# Digital_Output.net
KiCad netlist of a schematic drawn in Altium Designer
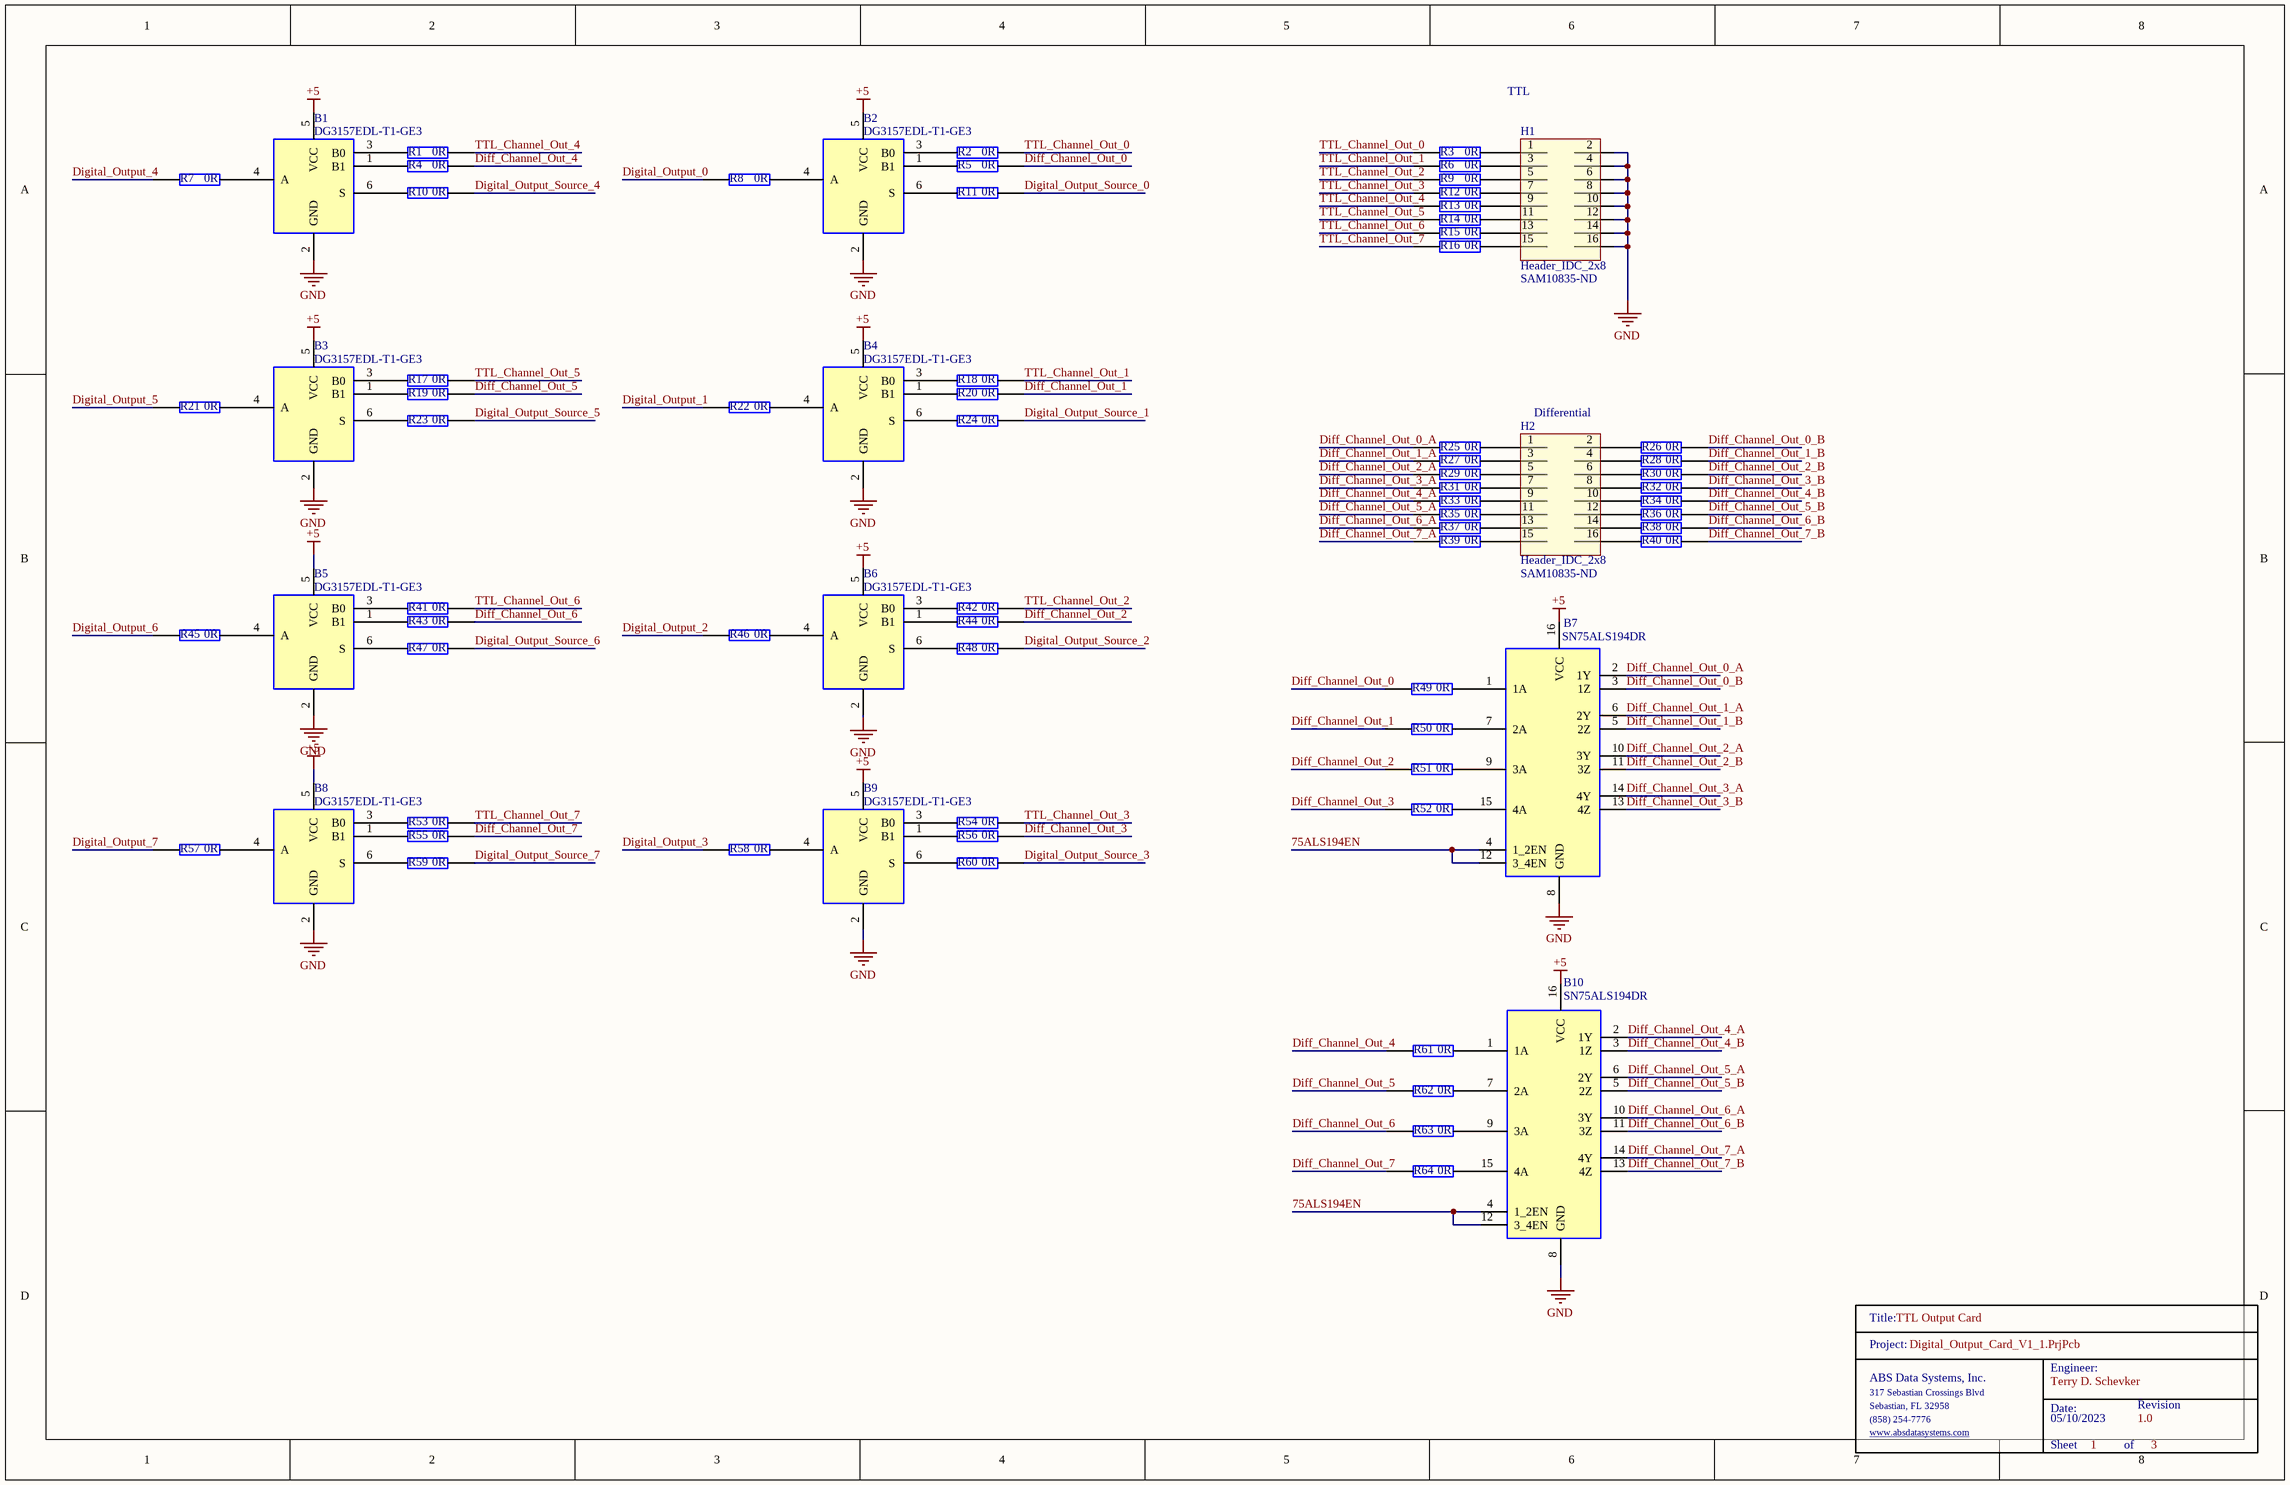
[diagram p0: Digital_Output.SchDoc]

(export (version "E")
  (design (tool "Eeschema 10.0.6"))
  (components
    (comp (ref "B1")
      (value "DG3157EDL-T1-GE3")
      (footprint "SOT65P210X110-6N")
      (description "Vishay DG3157EDL-T1-GE3 Analogue SPDT Switch 1.65 to 5.5 V, 6-Pin SC-70")
      (fields (field (name "MOUSER PART NUMBER") "78-DG3157EDL-T1-GE3"))
      (libsource (lib "SemiConductors") (part "DG3157EDL-T1-GE3"))
    )
    (comp (ref "B2")
      (value "DG3157EDL-T1-GE3")
      (footprint "SOT65P210X110-6N")
      (description "Vishay DG3157EDL-T1-GE3 Analogue SPDT Switch 1.65 to 5.5 V, 6-Pin SC-70")
      (fields (field (name "MOUSER PART NUMBER") "78-DG3157EDL-T1-GE3"))
      (libsource (lib "SemiConductors") (part "DG3157EDL-T1-GE3"))
    )
    (comp (ref "B3")
      (value "DG3157EDL-T1-GE3")
      (footprint "SOT65P210X110-6N")
      (description "Vishay DG3157EDL-T1-GE3 Analogue SPDT Switch 1.65 to 5.5 V, 6-Pin SC-70")
      (fields (field (name "MOUSER PART NUMBER") "78-DG3157EDL-T1-GE3"))
      (libsource (lib "SemiConductors") (part "DG3157EDL-T1-GE3"))
    )
    (comp (ref "B4")
      (value "DG3157EDL-T1-GE3")
      (footprint "SOT65P210X110-6N")
      (description "Vishay DG3157EDL-T1-GE3 Analogue SPDT Switch 1.65 to 5.5 V, 6-Pin SC-70")
      (fields (field (name "MOUSER PART NUMBER") "78-DG3157EDL-T1-GE3"))
      (libsource (lib "SemiConductors") (part "DG3157EDL-T1-GE3"))
    )
    (comp (ref "B5")
      (value "DG3157EDL-T1-GE3")
      (footprint "SOT65P210X110-6N")
      (description "Vishay DG3157EDL-T1-GE3 Analogue SPDT Switch 1.65 to 5.5 V, 6-Pin SC-70")
      (fields (field (name "MOUSER PART NUMBER") "78-DG3157EDL-T1-GE3"))
      (libsource (lib "SemiConductors") (part "DG3157EDL-T1-GE3"))
    )
    (comp (ref "B6")
      (value "DG3157EDL-T1-GE3")
      (footprint "SOT65P210X110-6N")
      (description "Vishay DG3157EDL-T1-GE3 Analogue SPDT Switch 1.65 to 5.5 V, 6-Pin SC-70")
      (fields (field (name "MOUSER PART NUMBER") "78-DG3157EDL-T1-GE3"))
      (libsource (lib "SemiConductors") (part "DG3157EDL-T1-GE3"))
    )
    (comp (ref "B7")
      (value "SN75ALS194DR")
      (footprint "SOIC127P600X175-16N")
      (description "Quadruple Differential Line Driver")
      (fields (field (name "MOUSER PART NUMBER") "595-SN75ALS194DR"))
      (libsource (lib "SemiConductors") (part "SN75ALS194DR"))
    )
    (comp (ref "B8")
      (value "DG3157EDL-T1-GE3")
      (footprint "SOT65P210X110-6N")
      (description "Vishay DG3157EDL-T1-GE3 Analogue SPDT Switch 1.65 to 5.5 V, 6-Pin SC-70")
      (fields (field (name "MOUSER PART NUMBER") "78-DG3157EDL-T1-GE3"))
      (libsource (lib "SemiConductors") (part "DG3157EDL-T1-GE3"))
    )
    (comp (ref "B9")
      (value "DG3157EDL-T1-GE3")
      (footprint "SOT65P210X110-6N")
      (description "Vishay DG3157EDL-T1-GE3 Analogue SPDT Switch 1.65 to 5.5 V, 6-Pin SC-70")
      (fields (field (name "MOUSER PART NUMBER") "78-DG3157EDL-T1-GE3"))
      (libsource (lib "SemiConductors") (part "DG3157EDL-T1-GE3"))
    )
    (comp (ref "B10")
      (value "SN75ALS194DR")
      (footprint "SOIC127P600X175-16N")
      (description "Quadruple Differential Line Driver")
      (fields (field (name "MOUSER PART NUMBER") "595-SN75ALS194DR"))
      (libsource (lib "SemiConductors") (part "SN75ALS194DR"))
    )
    (comp (ref "H1")
      (value "Header_IDC_2x8")
      (footprint "HDR2X8")
      (description "16 Pin 2x8 Through Hold IDC Connector")
      (fields
        (field (name "MANUFACTURER") "Samtec")
        (field (name "MANUFACTURER PART NUMBER") "TST-108-01-G-D")
        (field (name "SUPPLIER PART NUMBER 1") "SAM10835-ND")
      )
      (libsource (lib "Misc") (part "Header_IDC_2x8"))
    )
    (comp (ref "H2")
      (value "Header_IDC_2x8")
      (footprint "HDR2X8")
      (description "16 Pin 2x8 Through Hold IDC Connector")
      (fields
        (field (name "MANUFACTURER") "Samtec")
        (field (name "MANUFACTURER PART NUMBER") "TST-108-01-G-D")
        (field (name "SUPPLIER PART NUMBER 1") "SAM10835-ND")
      )
      (libsource (lib "Misc") (part "Header_IDC_2x8"))
    )
    (comp (ref "R1")
      (value "0R")
      (footprint "0603")
      (description "YAGEO 0603 0 ohm")
      (fields
        (field (name "MOUSER PART NUMBER") "603-RC0603JR-070RL")
        (field (name "MANUFACTURER_PART_NUMBER") "RC0603JR-070RL")
      )
      (libsource (lib "Resistors") (part "RC0603JR-070RL"))
    )
    (comp (ref "R2")
      (value "0R")
      (footprint "0603")
      (description "YAGEO 0603 0 ohm")
      (fields
        (field (name "MOUSER PART NUMBER") "603-RC0603JR-070RL")
        (field (name "MANUFACTURER_PART_NUMBER") "RC0603JR-070RL")
      )
      (libsource (lib "Resistors") (part "RC0603JR-070RL"))
    )
    (comp (ref "R3")
      (value "0R")
      (footprint "0603")
      (description "YAGEO 0603 0 ohm")
      (fields
        (field (name "MOUSER PART NUMBER") "603-RC0603JR-070RL")
        (field (name "MANUFACTURER_PART_NUMBER") "RC0603JR-070RL")
      )
      (libsource (lib "Resistors") (part "RC0603JR-070RL"))
    )
    (comp (ref "R4")
      (value "0R")
      (footprint "0603")
      (description "YAGEO 0603 0 ohm")
      (fields
        (field (name "MOUSER PART NUMBER") "603-RC0603JR-070RL")
        (field (name "MANUFACTURER_PART_NUMBER") "RC0603JR-070RL")
      )
      (libsource (lib "Resistors") (part "RC0603JR-070RL"))
    )
    (comp (ref "R5")
      (value "0R")
      (footprint "0603")
      (description "YAGEO 0603 0 ohm")
      (fields
        (field (name "MOUSER PART NUMBER") "603-RC0603JR-070RL")
        (field (name "MANUFACTURER_PART_NUMBER") "RC0603JR-070RL")
      )
      (libsource (lib "Resistors") (part "RC0603JR-070RL"))
    )
    (comp (ref "R6")
      (value "0R")
      (footprint "0603")
      (description "YAGEO 0603 0 ohm")
      (fields
        (field (name "MOUSER PART NUMBER") "603-RC0603JR-070RL")
        (field (name "MANUFACTURER_PART_NUMBER") "RC0603JR-070RL")
      )
      (libsource (lib "Resistors") (part "RC0603JR-070RL"))
    )
    (comp (ref "R7")
      (value "0R")
      (footprint "0603")
      (description "YAGEO 0603 0 ohm")
      (fields
        (field (name "MOUSER PART NUMBER") "603-RC0603JR-070RL")
        (field (name "MANUFACTURER_PART_NUMBER") "RC0603JR-070RL")
      )
      (libsource (lib "Resistors") (part "RC0603JR-070RL"))
    )
    (comp (ref "R8")
      (value "0R")
      (footprint "0603")
      (description "YAGEO 0603 0 ohm")
      (fields
        (field (name "MOUSER PART NUMBER") "603-RC0603JR-070RL")
        (field (name "MANUFACTURER_PART_NUMBER") "RC0603JR-070RL")
      )
      (libsource (lib "Resistors") (part "RC0603JR-070RL"))
    )
    (comp (ref "R9")
      (value "0R")
      (footprint "0603")
      (description "YAGEO 0603 0 ohm")
      (fields
        (field (name "MOUSER PART NUMBER") "603-RC0603JR-070RL")
        (field (name "MANUFACTURER_PART_NUMBER") "RC0603JR-070RL")
      )
      (libsource (lib "Resistors") (part "RC0603JR-070RL"))
    )
    (comp (ref "R10")
      (value "0R")
      (footprint "0603")
      (description "YAGEO 0603 0 ohm")
      (fields
        (field (name "MOUSER PART NUMBER") "603-RC0603JR-070RL")
        (field (name "MANUFACTURER_PART_NUMBER") "RC0603JR-070RL")
      )
      (libsource (lib "Resistors") (part "RC0603JR-070RL"))
    )
    (comp (ref "R11")
      (value "0R")
      (footprint "0603")
      (description "YAGEO 0603 0 ohm")
      (fields
        (field (name "MOUSER PART NUMBER") "603-RC0603JR-070RL")
        (field (name "MANUFACTURER_PART_NUMBER") "RC0603JR-070RL")
      )
      (libsource (lib "Resistors") (part "RC0603JR-070RL"))
    )
    (comp (ref "R12")
      (value "0R")
      (footprint "0603")
      (description "YAGEO 0603 0 ohm")
      (fields
        (field (name "MOUSER PART NUMBER") "603-RC0603JR-070RL")
        (field (name "MANUFACTURER_PART_NUMBER") "RC0603JR-070RL")
      )
      (libsource (lib "Resistors") (part "RC0603JR-070RL"))
    )
    (comp (ref "R13")
      (value "0R")
      (footprint "0603")
      (description "YAGEO 0603 0 ohm")
      (fields
        (field (name "MOUSER PART NUMBER") "603-RC0603JR-070RL")
        (field (name "MANUFACTURER_PART_NUMBER") "RC0603JR-070RL")
      )
      (libsource (lib "Resistors") (part "RC0603JR-070RL"))
    )
    (comp (ref "R14")
      (value "0R")
      (footprint "0603")
      (description "YAGEO 0603 0 ohm")
      (fields
        (field (name "MOUSER PART NUMBER") "603-RC0603JR-070RL")
        (field (name "MANUFACTURER_PART_NUMBER") "RC0603JR-070RL")
      )
      (libsource (lib "Resistors") (part "RC0603JR-070RL"))
    )
    (comp (ref "R15")
      (value "0R")
      (footprint "0603")
      (description "YAGEO 0603 0 ohm")
      (fields
        (field (name "MOUSER PART NUMBER") "603-RC0603JR-070RL")
        (field (name "MANUFACTURER_PART_NUMBER") "RC0603JR-070RL")
      )
      (libsource (lib "Resistors") (part "RC0603JR-070RL"))
    )
    (comp (ref "R16")
      (value "0R")
      (footprint "0603")
      (description "YAGEO 0603 0 ohm")
      (fields
        (field (name "MOUSER PART NUMBER") "603-RC0603JR-070RL")
        (field (name "MANUFACTURER_PART_NUMBER") "RC0603JR-070RL")
      )
      (libsource (lib "Resistors") (part "RC0603JR-070RL"))
    )
    (comp (ref "R17")
      (value "0R")
      (footprint "0603")
      (description "YAGEO 0603 0 ohm")
      (fields
        (field (name "MOUSER PART NUMBER") "603-RC0603JR-070RL")
        (field (name "MANUFACTURER_PART_NUMBER") "RC0603JR-070RL")
      )
      (libsource (lib "Resistors") (part "RC0603JR-070RL"))
    )
    (comp (ref "R18")
      (value "0R")
      (footprint "0603")
      (description "YAGEO 0603 0 ohm")
      (fields
        (field (name "MOUSER PART NUMBER") "603-RC0603JR-070RL")
        (field (name "MANUFACTURER_PART_NUMBER") "RC0603JR-070RL")
      )
      (libsource (lib "Resistors") (part "RC0603JR-070RL"))
    )
    (comp (ref "R19")
      (value "0R")
      (footprint "0603")
      (description "YAGEO 0603 0 ohm")
      (fields
        (field (name "MOUSER PART NUMBER") "603-RC0603JR-070RL")
        (field (name "MANUFACTURER_PART_NUMBER") "RC0603JR-070RL")
      )
      (libsource (lib "Resistors") (part "RC0603JR-070RL"))
    )
    (comp (ref "R20")
      (value "0R")
      (footprint "0603")
      (description "YAGEO 0603 0 ohm")
      (fields
        (field (name "MOUSER PART NUMBER") "603-RC0603JR-070RL")
        (field (name "MANUFACTURER_PART_NUMBER") "RC0603JR-070RL")
      )
      (libsource (lib "Resistors") (part "RC0603JR-070RL"))
    )
    (comp (ref "R21")
      (value "0R")
      (footprint "0603")
      (description "YAGEO 0603 0 ohm")
      (fields
        (field (name "MOUSER PART NUMBER") "603-RC0603JR-070RL")
        (field (name "MANUFACTURER_PART_NUMBER") "RC0603JR-070RL")
      )
      (libsource (lib "Resistors") (part "RC0603JR-070RL"))
    )
    (comp (ref "R22")
      (value "0R")
      (footprint "0603")
      (description "YAGEO 0603 0 ohm")
      (fields
        (field (name "MOUSER PART NUMBER") "603-RC0603JR-070RL")
        (field (name "MANUFACTURER_PART_NUMBER") "RC0603JR-070RL")
      )
      (libsource (lib "Resistors") (part "RC0603JR-070RL"))
    )
    (comp (ref "R23")
      (value "0R")
      (footprint "0603")
      (description "YAGEO 0603 0 ohm")
      (fields
        (field (name "MOUSER PART NUMBER") "603-RC0603JR-070RL")
        (field (name "MANUFACTURER_PART_NUMBER") "RC0603JR-070RL")
      )
      (libsource (lib "Resistors") (part "RC0603JR-070RL"))
    )
    (comp (ref "R24")
      (value "0R")
      (footprint "0603")
      (description "YAGEO 0603 0 ohm")
      (fields
        (field (name "MOUSER PART NUMBER") "603-RC0603JR-070RL")
        (field (name "MANUFACTURER_PART_NUMBER") "RC0603JR-070RL")
      )
      (libsource (lib "Resistors") (part "RC0603JR-070RL"))
    )
    (comp (ref "R25")
      (value "0R")
      (footprint "0603")
      (description "YAGEO 0603 0 ohm")
      (fields
        (field (name "MOUSER PART NUMBER") "603-RC0603JR-070RL")
        (field (name "MANUFACTURER_PART_NUMBER") "RC0603JR-070RL")
      )
      (libsource (lib "Resistors") (part "RC0603JR-070RL"))
    )
    (comp (ref "R26")
      (value "0R")
      (footprint "0603")
      (description "YAGEO 0603 0 ohm")
      (fields
        (field (name "MOUSER PART NUMBER") "603-RC0603JR-070RL")
        (field (name "MANUFACTURER_PART_NUMBER") "RC0603JR-070RL")
      )
      (libsource (lib "Resistors") (part "RC0603JR-070RL"))
    )
    (comp (ref "R27")
      (value "0R")
      (footprint "0603")
      (description "YAGEO 0603 0 ohm")
      (fields
        (field (name "MOUSER PART NUMBER") "603-RC0603JR-070RL")
        (field (name "MANUFACTURER_PART_NUMBER") "RC0603JR-070RL")
      )
      (libsource (lib "Resistors") (part "RC0603JR-070RL"))
    )
    (comp (ref "R28")
      (value "0R")
      (footprint "0603")
      (description "YAGEO 0603 0 ohm")
      (fields
        (field (name "MOUSER PART NUMBER") "603-RC0603JR-070RL")
        (field (name "MANUFACTURER_PART_NUMBER") "RC0603JR-070RL")
      )
      (libsource (lib "Resistors") (part "RC0603JR-070RL"))
    )
    (comp (ref "R29")
      (value "0R")
      (footprint "0603")
      (description "YAGEO 0603 0 ohm")
      (fields
        (field (name "MOUSER PART NUMBER") "603-RC0603JR-070RL")
        (field (name "MANUFACTURER_PART_NUMBER") "RC0603JR-070RL")
      )
      (libsource (lib "Resistors") (part "RC0603JR-070RL"))
    )
    (comp (ref "R30")
      (value "0R")
      (footprint "0603")
      (description "YAGEO 0603 0 ohm")
      (fields
        (field (name "MOUSER PART NUMBER") "603-RC0603JR-070RL")
        (field (name "MANUFACTURER_PART_NUMBER") "RC0603JR-070RL")
      )
      (libsource (lib "Resistors") (part "RC0603JR-070RL"))
    )
    (comp (ref "R31")
      (value "0R")
      (footprint "0603")
      (description "YAGEO 0603 0 ohm")
      (fields
        (field (name "MOUSER PART NUMBER") "603-RC0603JR-070RL")
        (field (name "MANUFACTURER_PART_NUMBER") "RC0603JR-070RL")
      )
      (libsource (lib "Resistors") (part "RC0603JR-070RL"))
    )
    (comp (ref "R32")
      (value "0R")
      (footprint "0603")
      (description "YAGEO 0603 0 ohm")
      (fields
        (field (name "MOUSER PART NUMBER") "603-RC0603JR-070RL")
        (field (name "MANUFACTURER_PART_NUMBER") "RC0603JR-070RL")
      )
      (libsource (lib "Resistors") (part "RC0603JR-070RL"))
    )
    (comp (ref "R33")
      (value "0R")
      (footprint "0603")
      (description "YAGEO 0603 0 ohm")
      (fields
        (field (name "MOUSER PART NUMBER") "603-RC0603JR-070RL")
        (field (name "MANUFACTURER_PART_NUMBER") "RC0603JR-070RL")
      )
      (libsource (lib "Resistors") (part "RC0603JR-070RL"))
    )
    (comp (ref "R34")
      (value "0R")
      (footprint "0603")
      (description "YAGEO 0603 0 ohm")
      (fields
        (field (name "MOUSER PART NUMBER") "603-RC0603JR-070RL")
        (field (name "MANUFACTURER_PART_NUMBER") "RC0603JR-070RL")
      )
      (libsource (lib "Resistors") (part "RC0603JR-070RL"))
    )
    (comp (ref "R35")
      (value "0R")
      (footprint "0603")
      (description "YAGEO 0603 0 ohm")
      (fields
        (field (name "MOUSER PART NUMBER") "603-RC0603JR-070RL")
        (field (name "MANUFACTURER_PART_NUMBER") "RC0603JR-070RL")
      )
      (libsource (lib "Resistors") (part "RC0603JR-070RL"))
    )
    (comp (ref "R36")
      (value "0R")
      (footprint "0603")
      (description "YAGEO 0603 0 ohm")
      (fields
        (field (name "MOUSER PART NUMBER") "603-RC0603JR-070RL")
        (field (name "MANUFACTURER_PART_NUMBER") "RC0603JR-070RL")
      )
      (libsource (lib "Resistors") (part "RC0603JR-070RL"))
    )
    (comp (ref "R37")
      (value "0R")
      (footprint "0603")
      (description "YAGEO 0603 0 ohm")
      (fields
        (field (name "MOUSER PART NUMBER") "603-RC0603JR-070RL")
        (field (name "MANUFACTURER_PART_NUMBER") "RC0603JR-070RL")
      )
      (libsource (lib "Resistors") (part "RC0603JR-070RL"))
    )
    (comp (ref "R38")
      (value "0R")
      (footprint "0603")
      (description "YAGEO 0603 0 ohm")
      (fields
        (field (name "MOUSER PART NUMBER") "603-RC0603JR-070RL")
        (field (name "MANUFACTURER_PART_NUMBER") "RC0603JR-070RL")
      )
      (libsource (lib "Resistors") (part "RC0603JR-070RL"))
    )
    (comp (ref "R39")
      (value "0R")
      (footprint "0603")
      (description "YAGEO 0603 0 ohm")
      (fields
        (field (name "MOUSER PART NUMBER") "603-RC0603JR-070RL")
        (field (name "MANUFACTURER_PART_NUMBER") "RC0603JR-070RL")
      )
      (libsource (lib "Resistors") (part "RC0603JR-070RL"))
    )
    (comp (ref "R40")
      (value "0R")
      (footprint "0603")
      (description "YAGEO 0603 0 ohm")
      (fields
        (field (name "MOUSER PART NUMBER") "603-RC0603JR-070RL")
        (field (name "MANUFACTURER_PART_NUMBER") "RC0603JR-070RL")
      )
      (libsource (lib "Resistors") (part "RC0603JR-070RL"))
    )
    (comp (ref "R41")
      (value "0R")
      (footprint "0603")
      (description "YAGEO 0603 0 ohm")
      (fields
        (field (name "MOUSER PART NUMBER") "603-RC0603JR-070RL")
        (field (name "MANUFACTURER_PART_NUMBER") "RC0603JR-070RL")
      )
      (libsource (lib "Resistors") (part "RC0603JR-070RL"))
    )
    (comp (ref "R42")
      (value "0R")
      (footprint "0603")
      (description "YAGEO 0603 0 ohm")
      (fields
        (field (name "MOUSER PART NUMBER") "603-RC0603JR-070RL")
        (field (name "MANUFACTURER_PART_NUMBER") "RC0603JR-070RL")
      )
      (libsource (lib "Resistors") (part "RC0603JR-070RL"))
    )
    (comp (ref "R43")
      (value "0R")
      (footprint "0603")
      (description "YAGEO 0603 0 ohm")
      (fields
        (field (name "MOUSER PART NUMBER") "603-RC0603JR-070RL")
        (field (name "MANUFACTURER_PART_NUMBER") "RC0603JR-070RL")
      )
      (libsource (lib "Resistors") (part "RC0603JR-070RL"))
    )
    (comp (ref "R44")
      (value "0R")
      (footprint "0603")
      (description "YAGEO 0603 0 ohm")
      (fields
        (field (name "MOUSER PART NUMBER") "603-RC0603JR-070RL")
        (field (name "MANUFACTURER_PART_NUMBER") "RC0603JR-070RL")
      )
      (libsource (lib "Resistors") (part "RC0603JR-070RL"))
    )
    (comp (ref "R45")
      (value "0R")
      (footprint "0603")
      (description "YAGEO 0603 0 ohm")
      (fields
        (field (name "MOUSER PART NUMBER") "603-RC0603JR-070RL")
        (field (name "MANUFACTURER_PART_NUMBER") "RC0603JR-070RL")
      )
      (libsource (lib "Resistors") (part "RC0603JR-070RL"))
    )
    (comp (ref "R46")
      (value "0R")
      (footprint "0603")
      (description "YAGEO 0603 0 ohm")
      (fields
        (field (name "MOUSER PART NUMBER") "603-RC0603JR-070RL")
        (field (name "MANUFACTURER_PART_NUMBER") "RC0603JR-070RL")
      )
      (libsource (lib "Resistors") (part "RC0603JR-070RL"))
    )
    (comp (ref "R47")
      (value "0R")
      (footprint "0603")
      (description "YAGEO 0603 0 ohm")
      (fields
        (field (name "MOUSER PART NUMBER") "603-RC0603JR-070RL")
        (field (name "MANUFACTURER_PART_NUMBER") "RC0603JR-070RL")
      )
      (libsource (lib "Resistors") (part "RC0603JR-070RL"))
    )
    (comp (ref "R48")
      (value "0R")
      (footprint "0603")
      (description "YAGEO 0603 0 ohm")
      (fields
        (field (name "MOUSER PART NUMBER") "603-RC0603JR-070RL")
        (field (name "MANUFACTURER_PART_NUMBER") "RC0603JR-070RL")
      )
      (libsource (lib "Resistors") (part "RC0603JR-070RL"))
    )
    (comp (ref "R49")
      (value "0R")
      (footprint "0603")
      (description "YAGEO 0603 0 ohm")
      (fields
        (field (name "MOUSER PART NUMBER") "603-RC0603JR-070RL")
        (field (name "MANUFACTURER_PART_NUMBER") "RC0603JR-070RL")
      )
      (libsource (lib "Resistors") (part "RC0603JR-070RL"))
    )
    (comp (ref "R50")
      (value "0R")
      (footprint "0603")
      (description "YAGEO 0603 0 ohm")
      (fields
        (field (name "MOUSER PART NUMBER") "603-RC0603JR-070RL")
        (field (name "MANUFACTURER_PART_NUMBER") "RC0603JR-070RL")
      )
      (libsource (lib "Resistors") (part "RC0603JR-070RL"))
    )
    (comp (ref "R51")
      (value "0R")
      (footprint "0603")
      (description "YAGEO 0603 0 ohm")
      (fields
        (field (name "MOUSER PART NUMBER") "603-RC0603JR-070RL")
        (field (name "MANUFACTURER_PART_NUMBER") "RC0603JR-070RL")
      )
      (libsource (lib "Resistors") (part "RC0603JR-070RL"))
    )
    (comp (ref "R52")
      (value "0R")
      (footprint "0603")
      (description "YAGEO 0603 0 ohm")
      (fields
        (field (name "MOUSER PART NUMBER") "603-RC0603JR-070RL")
        (field (name "MANUFACTURER_PART_NUMBER") "RC0603JR-070RL")
      )
      (libsource (lib "Resistors") (part "RC0603JR-070RL"))
    )
    (comp (ref "R53")
      (value "0R")
      (footprint "0603")
      (description "YAGEO 0603 0 ohm")
      (fields
        (field (name "MOUSER PART NUMBER") "603-RC0603JR-070RL")
        (field (name "MANUFACTURER_PART_NUMBER") "RC0603JR-070RL")
      )
      (libsource (lib "Resistors") (part "RC0603JR-070RL"))
    )
    (comp (ref "R54")
      (value "0R")
      (footprint "0603")
      (description "YAGEO 0603 0 ohm")
      (fields
        (field (name "MOUSER PART NUMBER") "603-RC0603JR-070RL")
        (field (name "MANUFACTURER_PART_NUMBER") "RC0603JR-070RL")
      )
      (libsource (lib "Resistors") (part "RC0603JR-070RL"))
    )
    (comp (ref "R55")
      (value "0R")
      (footprint "0603")
      (description "YAGEO 0603 0 ohm")
      (fields
        (field (name "MOUSER PART NUMBER") "603-RC0603JR-070RL")
        (field (name "MANUFACTURER_PART_NUMBER") "RC0603JR-070RL")
      )
      (libsource (lib "Resistors") (part "RC0603JR-070RL"))
    )
    (comp (ref "R56")
      (value "0R")
      (footprint "0603")
      (description "YAGEO 0603 0 ohm")
      (fields
        (field (name "MOUSER PART NUMBER") "603-RC0603JR-070RL")
        (field (name "MANUFACTURER_PART_NUMBER") "RC0603JR-070RL")
      )
      (libsource (lib "Resistors") (part "RC0603JR-070RL"))
    )
    (comp (ref "R57")
      (value "0R")
      (footprint "0603")
      (description "YAGEO 0603 0 ohm")
      (fields
        (field (name "MOUSER PART NUMBER") "603-RC0603JR-070RL")
        (field (name "MANUFACTURER_PART_NUMBER") "RC0603JR-070RL")
      )
      (libsource (lib "Resistors") (part "RC0603JR-070RL"))
    )
    (comp (ref "R58")
      (value "0R")
      (footprint "0603")
      (description "YAGEO 0603 0 ohm")
      (fields
        (field (name "MOUSER PART NUMBER") "603-RC0603JR-070RL")
        (field (name "MANUFACTURER_PART_NUMBER") "RC0603JR-070RL")
      )
      (libsource (lib "Resistors") (part "RC0603JR-070RL"))
    )
    (comp (ref "R59")
      (value "0R")
      (footprint "0603")
      (description "YAGEO 0603 0 ohm")
      (fields
        (field (name "MOUSER PART NUMBER") "603-RC0603JR-070RL")
        (field (name "MANUFACTURER_PART_NUMBER") "RC0603JR-070RL")
      )
      (libsource (lib "Resistors") (part "RC0603JR-070RL"))
    )
    (comp (ref "R60")
      (value "0R")
      (footprint "0603")
      (description "YAGEO 0603 0 ohm")
      (fields
        (field (name "MOUSER PART NUMBER") "603-RC0603JR-070RL")
        (field (name "MANUFACTURER_PART_NUMBER") "RC0603JR-070RL")
      )
      (libsource (lib "Resistors") (part "RC0603JR-070RL"))
    )
    (comp (ref "R61")
      (value "0R")
      (footprint "0603")
      (description "YAGEO 0603 0 ohm")
      (fields
        (field (name "MOUSER PART NUMBER") "603-RC0603JR-070RL")
        (field (name "MANUFACTURER_PART_NUMBER") "RC0603JR-070RL")
      )
      (libsource (lib "Resistors") (part "RC0603JR-070RL"))
    )
    (comp (ref "R62")
      (value "0R")
      (footprint "0603")
      (description "YAGEO 0603 0 ohm")
      (fields
        (field (name "MOUSER PART NUMBER") "603-RC0603JR-070RL")
        (field (name "MANUFACTURER_PART_NUMBER") "RC0603JR-070RL")
      )
      (libsource (lib "Resistors") (part "RC0603JR-070RL"))
    )
    (comp (ref "R63")
      (value "0R")
      (footprint "0603")
      (description "YAGEO 0603 0 ohm")
      (fields
        (field (name "MOUSER PART NUMBER") "603-RC0603JR-070RL")
        (field (name "MANUFACTURER_PART_NUMBER") "RC0603JR-070RL")
      )
      (libsource (lib "Resistors") (part "RC0603JR-070RL"))
    )
    (comp (ref "R64")
      (value "0R")
      (footprint "0603")
      (description "YAGEO 0603 0 ohm")
      (fields
        (field (name "MOUSER PART NUMBER") "603-RC0603JR-070RL")
        (field (name "MANUFACTURER_PART_NUMBER") "RC0603JR-070RL")
      )
      (libsource (lib "Resistors") (part "RC0603JR-070RL"))
    )
    (comp (ref "TitleBlock_3") (value "TitleBlock") (libsource (lib "Misc") (part "TitleBlock")))
  )
  (nets
    (net (code "1") (name "+5") (class "Default")
      (node (ref "B1") (pin "5") (pinfunction "VCC_5") (pintype "passive"))
      (node (ref "B10") (pin "16") (pinfunction "VCC_16") (pintype "passive"))
      (node (ref "B2") (pin "5") (pinfunction "VCC_5") (pintype "passive"))
      (node (ref "B3") (pin "5") (pinfunction "VCC_5") (pintype "passive"))
      (node (ref "B4") (pin "5") (pinfunction "VCC_5") (pintype "passive"))
      (node (ref "B5") (pin "5") (pinfunction "VCC_5") (pintype "passive"))
      (node (ref "B6") (pin "5") (pinfunction "VCC_5") (pintype "passive"))
      (node (ref "B7") (pin "16") (pinfunction "VCC_16") (pintype "passive"))
      (node (ref "B8") (pin "5") (pinfunction "VCC_5") (pintype "passive"))
      (node (ref "B9") (pin "5") (pinfunction "VCC_5") (pintype "passive"))
    )
    (net (code "2") (name "/75ALS194EN") (class "Default")
      (node (ref "B10") (pin "12") (pinfunction "3_4EN_12") (pintype "passive"))
      (node (ref "B10") (pin "4") (pinfunction "1_2EN_4") (pintype "passive"))
      (node (ref "B7") (pin "12") (pinfunction "3_4EN_12") (pintype "passive"))
      (node (ref "B7") (pin "4") (pinfunction "1_2EN_4") (pintype "passive"))
    )
    (net (code "3") (name "/Diff_Channel_Out_0") (class "Default")
      (node (ref "R49") (pin "1") (pinfunction "1_1") (pintype "passive"))
      (node (ref "R5") (pin "2") (pinfunction "2_2") (pintype "passive"))
    )
    (net (code "4") (name "/Diff_Channel_Out_0_A") (class "Default")
      (node (ref "B7") (pin "2") (pinfunction "1Y_2") (pintype "passive"))
      (node (ref "R25") (pin "1") (pinfunction "1_1") (pintype "passive"))
    )
    (net (code "5") (name "/Diff_Channel_Out_0_B") (class "Default")
      (node (ref "B7") (pin "3") (pinfunction "1Z_3") (pintype "passive"))
      (node (ref "R26") (pin "2") (pinfunction "2_2") (pintype "passive"))
    )
    (net (code "6") (name "/Diff_Channel_Out_1") (class "Default")
      (node (ref "R20") (pin "2") (pinfunction "2_2") (pintype "passive"))
      (node (ref "R50") (pin "1") (pinfunction "1_1") (pintype "passive"))
    )
    (net (code "7") (name "/Diff_Channel_Out_1_A") (class "Default")
      (node (ref "B7") (pin "6") (pinfunction "2Y_6") (pintype "passive"))
      (node (ref "R27") (pin "1") (pinfunction "1_1") (pintype "passive"))
    )
    (net (code "8") (name "/Diff_Channel_Out_1_B") (class "Default")
      (node (ref "B7") (pin "5") (pinfunction "2Z_5") (pintype "passive"))
      (node (ref "R28") (pin "2") (pinfunction "2_2") (pintype "passive"))
    )
    (net (code "9") (name "/Diff_Channel_Out_2") (class "Default")
      (node (ref "R44") (pin "2") (pinfunction "2_2") (pintype "passive"))
      (node (ref "R51") (pin "1") (pinfunction "1_1") (pintype "passive"))
    )
    (net (code "10") (name "/Diff_Channel_Out_2_A") (class "Default")
      (node (ref "B7") (pin "10") (pinfunction "3Y_10") (pintype "passive"))
      (node (ref "R29") (pin "1") (pinfunction "1_1") (pintype "passive"))
    )
    (net (code "11") (name "/Diff_Channel_Out_2_B") (class "Default")
      (node (ref "B7") (pin "11") (pinfunction "3Z_11") (pintype "passive"))
      (node (ref "R30") (pin "2") (pinfunction "2_2") (pintype "passive"))
    )
    (net (code "12") (name "/Diff_Channel_Out_3") (class "Default")
      (node (ref "R52") (pin "1") (pinfunction "1_1") (pintype "passive"))
      (node (ref "R56") (pin "2") (pinfunction "2_2") (pintype "passive"))
    )
    (net (code "13") (name "/Diff_Channel_Out_3_A") (class "Default")
      (node (ref "B7") (pin "14") (pinfunction "4Y_14") (pintype "passive"))
      (node (ref "R31") (pin "1") (pinfunction "1_1") (pintype "passive"))
    )
    (net (code "14") (name "/Diff_Channel_Out_3_B") (class "Default")
      (node (ref "B7") (pin "13") (pinfunction "4Z_13") (pintype "passive"))
      (node (ref "R32") (pin "2") (pinfunction "2_2") (pintype "passive"))
    )
    (net (code "15") (name "/Diff_Channel_Out_4") (class "Default")
      (node (ref "R4") (pin "2") (pinfunction "2_2") (pintype "passive"))
      (node (ref "R61") (pin "1") (pinfunction "1_1") (pintype "passive"))
    )
    (net (code "16") (name "/Diff_Channel_Out_4_A") (class "Default")
      (node (ref "B10") (pin "2") (pinfunction "1Y_2") (pintype "passive"))
      (node (ref "R33") (pin "1") (pinfunction "1_1") (pintype "passive"))
    )
    (net (code "17") (name "/Diff_Channel_Out_4_B") (class "Default")
      (node (ref "B10") (pin "3") (pinfunction "1Z_3") (pintype "passive"))
      (node (ref "R34") (pin "2") (pinfunction "2_2") (pintype "passive"))
    )
    (net (code "18") (name "/Diff_Channel_Out_5") (class "Default")
      (node (ref "R19") (pin "2") (pinfunction "2_2") (pintype "passive"))
      (node (ref "R62") (pin "1") (pinfunction "1_1") (pintype "passive"))
    )
    (net (code "19") (name "/Diff_Channel_Out_5_A") (class "Default")
      (node (ref "B10") (pin "6") (pinfunction "2Y_6") (pintype "passive"))
      (node (ref "R35") (pin "1") (pinfunction "1_1") (pintype "passive"))
    )
    (net (code "20") (name "/Diff_Channel_Out_5_B") (class "Default")
      (node (ref "B10") (pin "5") (pinfunction "2Z_5") (pintype "passive"))
      (node (ref "R36") (pin "2") (pinfunction "2_2") (pintype "passive"))
    )
    (net (code "21") (name "/Diff_Channel_Out_6") (class "Default")
      (node (ref "R43") (pin "2") (pinfunction "2_2") (pintype "passive"))
      (node (ref "R63") (pin "1") (pinfunction "1_1") (pintype "passive"))
    )
    (net (code "22") (name "/Diff_Channel_Out_6_A") (class "Default")
      (node (ref "B10") (pin "10") (pinfunction "3Y_10") (pintype "passive"))
      (node (ref "R37") (pin "1") (pinfunction "1_1") (pintype "passive"))
    )
    (net (code "23") (name "/Diff_Channel_Out_6_B") (class "Default")
      (node (ref "B10") (pin "11") (pinfunction "3Z_11") (pintype "passive"))
      (node (ref "R38") (pin "2") (pinfunction "2_2") (pintype "passive"))
    )
    (net (code "24") (name "/Diff_Channel_Out_7") (class "Default")
      (node (ref "R55") (pin "2") (pinfunction "2_2") (pintype "passive"))
      (node (ref "R64") (pin "1") (pinfunction "1_1") (pintype "passive"))
    )
    (net (code "25") (name "/Diff_Channel_Out_7_A") (class "Default")
      (node (ref "B10") (pin "14") (pinfunction "4Y_14") (pintype "passive"))
      (node (ref "R39") (pin "1") (pinfunction "1_1") (pintype "passive"))
    )
    (net (code "26") (name "/Diff_Channel_Out_7_B") (class "Default")
      (node (ref "B10") (pin "13") (pinfunction "4Z_13") (pintype "passive"))
      (node (ref "R40") (pin "2") (pinfunction "2_2") (pintype "passive"))
    )
    (net (code "27") (name "/Digital_Output_0") (class "Default")
      (node (ref "R8") (pin "1") (pinfunction "1_1") (pintype "passive"))
    )
    (net (code "28") (name "/Digital_Output_1") (class "Default")
      (node (ref "R22") (pin "1") (pinfunction "1_1") (pintype "passive"))
    )
    (net (code "29") (name "/Digital_Output_2") (class "Default")
      (node (ref "R46") (pin "1") (pinfunction "1_1") (pintype "passive"))
    )
    (net (code "30") (name "/Digital_Output_3") (class "Default")
      (node (ref "R58") (pin "1") (pinfunction "1_1") (pintype "passive"))
    )
    (net (code "31") (name "/Digital_Output_4") (class "Default")
      (node (ref "R7") (pin "1") (pinfunction "1_1") (pintype "passive"))
    )
    (net (code "32") (name "/Digital_Output_5") (class "Default")
      (node (ref "R21") (pin "1") (pinfunction "1_1") (pintype "passive"))
    )
    (net (code "33") (name "/Digital_Output_6") (class "Default")
      (node (ref "R45") (pin "1") (pinfunction "1_1") (pintype "passive"))
    )
    (net (code "34") (name "/Digital_Output_7") (class "Default")
      (node (ref "R57") (pin "1") (pinfunction "1_1") (pintype "passive"))
    )
    (net (code "35") (name "/Digital_Output_Source_0") (class "Default")
      (node (ref "R11") (pin "2") (pinfunction "2_2") (pintype "passive"))
    )
    (net (code "36") (name "/Digital_Output_Source_1") (class "Default")
      (node (ref "R24") (pin "2") (pinfunction "2_2") (pintype "passive"))
    )
    (net (code "37") (name "/Digital_Output_Source_2") (class "Default")
      (node (ref "R48") (pin "2") (pinfunction "2_2") (pintype "passive"))
    )
    (net (code "38") (name "/Digital_Output_Source_3") (class "Default")
      (node (ref "R60") (pin "2") (pinfunction "2_2") (pintype "passive"))
    )
    (net (code "39") (name "/Digital_Output_Source_4") (class "Default")
      (node (ref "R10") (pin "2") (pinfunction "2_2") (pintype "passive"))
    )
    (net (code "40") (name "/Digital_Output_Source_5") (class "Default")
      (node (ref "R23") (pin "2") (pinfunction "2_2") (pintype "passive"))
    )
    (net (code "41") (name "/Digital_Output_Source_6") (class "Default")
      (node (ref "R47") (pin "2") (pinfunction "2_2") (pintype "passive"))
    )
    (net (code "42") (name "/Digital_Output_Source_7") (class "Default")
      (node (ref "R59") (pin "2") (pinfunction "2_2") (pintype "passive"))
    )
    (net (code "43") (name "/TTL_Channel_Out_0") (class "Default")
      (node (ref "R2") (pin "2") (pinfunction "2_2") (pintype "passive"))
      (node (ref "R3") (pin "1") (pinfunction "1_1") (pintype "passive"))
    )
    (net (code "44") (name "/TTL_Channel_Out_1") (class "Default")
      (node (ref "R18") (pin "2") (pinfunction "2_2") (pintype "passive"))
      (node (ref "R6") (pin "1") (pinfunction "1_1") (pintype "passive"))
    )
    (net (code "45") (name "/TTL_Channel_Out_2") (class "Default")
      (node (ref "R42") (pin "2") (pinfunction "2_2") (pintype "passive"))
      (node (ref "R9") (pin "1") (pinfunction "1_1") (pintype "passive"))
    )
    (net (code "46") (name "/TTL_Channel_Out_3") (class "Default")
      (node (ref "R12") (pin "1") (pinfunction "1_1") (pintype "passive"))
      (node (ref "R54") (pin "2") (pinfunction "2_2") (pintype "passive"))
    )
    (net (code "47") (name "/TTL_Channel_Out_4") (class "Default")
      (node (ref "R1") (pin "2") (pinfunction "2_2") (pintype "passive"))
      (node (ref "R13") (pin "1") (pinfunction "1_1") (pintype "passive"))
    )
    (net (code "48") (name "/TTL_Channel_Out_5") (class "Default")
      (node (ref "R14") (pin "1") (pinfunction "1_1") (pintype "passive"))
      (node (ref "R17") (pin "2") (pinfunction "2_2") (pintype "passive"))
    )
    (net (code "49") (name "/TTL_Channel_Out_6") (class "Default")
      (node (ref "R15") (pin "1") (pinfunction "1_1") (pintype "passive"))
      (node (ref "R41") (pin "2") (pinfunction "2_2") (pintype "passive"))
    )
    (net (code "50") (name "/TTL_Channel_Out_7") (class "Default")
      (node (ref "R16") (pin "1") (pinfunction "1_1") (pintype "passive"))
      (node (ref "R53") (pin "2") (pinfunction "2_2") (pintype "passive"))
    )
    (net (code "51") (name "GND") (class "Default")
      (node (ref "B1") (pin "2") (pinfunction "GND_2") (pintype "passive"))
      (node (ref "B10") (pin "8") (pinfunction "GND_8") (pintype "passive"))
      (node (ref "B2") (pin "2") (pinfunction "GND_2") (pintype "passive"))
      (node (ref "B3") (pin "2") (pinfunction "GND_2") (pintype "passive"))
      (node (ref "B4") (pin "2") (pinfunction "GND_2") (pintype "passive"))
      (node (ref "B5") (pin "2") (pinfunction "GND_2") (pintype "passive"))
      (node (ref "B6") (pin "2") (pinfunction "GND_2") (pintype "passive"))
      (node (ref "B7") (pin "8") (pinfunction "GND_8") (pintype "passive"))
      (node (ref "B8") (pin "2") (pinfunction "GND_2") (pintype "passive"))
      (node (ref "B9") (pin "2") (pinfunction "GND_2") (pintype "passive"))
      (node (ref "H1") (pin "10") (pinfunction "10_10") (pintype "passive"))
      (node (ref "H1") (pin "12") (pinfunction "12_12") (pintype "passive"))
      (node (ref "H1") (pin "14") (pinfunction "14_14") (pintype "passive"))
      (node (ref "H1") (pin "16") (pinfunction "16_16") (pintype "passive"))
      (node (ref "H1") (pin "2") (pinfunction "2_2") (pintype "passive"))
      (node (ref "H1") (pin "4") (pinfunction "4_4") (pintype "passive"))
      (node (ref "H1") (pin "6") (pinfunction "6_6") (pintype "passive"))
      (node (ref "H1") (pin "8") (pinfunction "8_8") (pintype "passive"))
    )
    (net (code "52") (name "Net-(B1-A)") (class "Default")
      (node (ref "B1") (pin "4") (pinfunction "A_4") (pintype "passive"))
      (node (ref "R7") (pin "2") (pinfunction "2_2") (pintype "passive"))
    )
    (net (code "53") (name "Net-(B1-B0)") (class "Default")
      (node (ref "B1") (pin "3") (pinfunction "B0_3") (pintype "passive"))
      (node (ref "R1") (pin "1") (pinfunction "1_1") (pintype "passive"))
    )
    (net (code "54") (name "Net-(B1-B1)") (class "Default")
      (node (ref "B1") (pin "1") (pinfunction "B1_1") (pintype "passive"))
      (node (ref "R4") (pin "1") (pinfunction "1_1") (pintype "passive"))
    )
    (net (code "55") (name "Net-(B1-S)") (class "Default")
      (node (ref "B1") (pin "6") (pinfunction "S_6") (pintype "passive"))
      (node (ref "R10") (pin "1") (pinfunction "1_1") (pintype "passive"))
    )
    (net (code "56") (name "Net-(B2-A)") (class "Default")
      (node (ref "B2") (pin "4") (pinfunction "A_4") (pintype "passive"))
      (node (ref "R8") (pin "2") (pinfunction "2_2") (pintype "passive"))
    )
    (net (code "57") (name "Net-(B2-B0)") (class "Default")
      (node (ref "B2") (pin "3") (pinfunction "B0_3") (pintype "passive"))
      (node (ref "R2") (pin "1") (pinfunction "1_1") (pintype "passive"))
    )
    (net (code "58") (name "Net-(B2-B1)") (class "Default")
      (node (ref "B2") (pin "1") (pinfunction "B1_1") (pintype "passive"))
      (node (ref "R5") (pin "1") (pinfunction "1_1") (pintype "passive"))
    )
    (net (code "59") (name "Net-(B2-S)") (class "Default")
      (node (ref "B2") (pin "6") (pinfunction "S_6") (pintype "passive"))
      (node (ref "R11") (pin "1") (pinfunction "1_1") (pintype "passive"))
    )
    (net (code "60") (name "Net-(B3-A)") (class "Default")
      (node (ref "B3") (pin "4") (pinfunction "A_4") (pintype "passive"))
      (node (ref "R21") (pin "2") (pinfunction "2_2") (pintype "passive"))
    )
    (net (code "61") (name "Net-(B3-B0)") (class "Default")
      (node (ref "B3") (pin "3") (pinfunction "B0_3") (pintype "passive"))
      (node (ref "R17") (pin "1") (pinfunction "1_1") (pintype "passive"))
    )
    (net (code "62") (name "Net-(B3-B1)") (class "Default")
      (node (ref "B3") (pin "1") (pinfunction "B1_1") (pintype "passive"))
      (node (ref "R19") (pin "1") (pinfunction "1_1") (pintype "passive"))
    )
    (net (code "63") (name "Net-(B3-S)") (class "Default")
      (node (ref "B3") (pin "6") (pinfunction "S_6") (pintype "passive"))
      (node (ref "R23") (pin "1") (pinfunction "1_1") (pintype "passive"))
    )
    (net (code "64") (name "Net-(B4-A)") (class "Default")
      (node (ref "B4") (pin "4") (pinfunction "A_4") (pintype "passive"))
      (node (ref "R22") (pin "2") (pinfunction "2_2") (pintype "passive"))
    )
    (net (code "65") (name "Net-(B4-B0)") (class "Default")
      (node (ref "B4") (pin "3") (pinfunction "B0_3") (pintype "passive"))
      (node (ref "R18") (pin "1") (pinfunction "1_1") (pintype "passive"))
    )
    (net (code "66") (name "Net-(B4-B1)") (class "Default")
      (node (ref "B4") (pin "1") (pinfunction "B1_1") (pintype "passive"))
      (node (ref "R20") (pin "1") (pinfunction "1_1") (pintype "passive"))
    )
    (net (code "67") (name "Net-(B4-S)") (class "Default")
      (node (ref "B4") (pin "6") (pinfunction "S_6") (pintype "passive"))
      (node (ref "R24") (pin "1") (pinfunction "1_1") (pintype "passive"))
    )
    (net (code "68") (name "Net-(B5-A)") (class "Default")
      (node (ref "B5") (pin "4") (pinfunction "A_4") (pintype "passive"))
      (node (ref "R45") (pin "2") (pinfunction "2_2") (pintype "passive"))
    )
    (net (code "69") (name "Net-(B5-B0)") (class "Default")
      (node (ref "B5") (pin "3") (pinfunction "B0_3") (pintype "passive"))
      (node (ref "R41") (pin "1") (pinfunction "1_1") (pintype "passive"))
    )
    (net (code "70") (name "Net-(B5-B1)") (class "Default")
      (node (ref "B5") (pin "1") (pinfunction "B1_1") (pintype "passive"))
      (node (ref "R43") (pin "1") (pinfunction "1_1") (pintype "passive"))
    )
    (net (code "71") (name "Net-(B5-S)") (class "Default")
      (node (ref "B5") (pin "6") (pinfunction "S_6") (pintype "passive"))
      (node (ref "R47") (pin "1") (pinfunction "1_1") (pintype "passive"))
    )
    (net (code "72") (name "Net-(B6-A)") (class "Default")
      (node (ref "B6") (pin "4") (pinfunction "A_4") (pintype "passive"))
      (node (ref "R46") (pin "2") (pinfunction "2_2") (pintype "passive"))
    )
    (net (code "73") (name "Net-(B6-B0)") (class "Default")
      (node (ref "B6") (pin "3") (pinfunction "B0_3") (pintype "passive"))
      (node (ref "R42") (pin "1") (pinfunction "1_1") (pintype "passive"))
    )
    (net (code "74") (name "Net-(B6-B1)") (class "Default")
      (node (ref "B6") (pin "1") (pinfunction "B1_1") (pintype "passive"))
      (node (ref "R44") (pin "1") (pinfunction "1_1") (pintype "passive"))
    )
    (net (code "75") (name "Net-(B6-S)") (class "Default")
      (node (ref "B6") (pin "6") (pinfunction "S_6") (pintype "passive"))
      (node (ref "R48") (pin "1") (pinfunction "1_1") (pintype "passive"))
    )
    (net (code "76") (name "Net-(B7-1A)") (class "Default")
      (node (ref "B7") (pin "1") (pinfunction "1A_1") (pintype "passive"))
      (node (ref "R49") (pin "2") (pinfunction "2_2") (pintype "passive"))
    )
    (net (code "77") (name "Net-(B7-2A)") (class "Default")
      (node (ref "B7") (pin "7") (pinfunction "2A_7") (pintype "passive"))
      (node (ref "R50") (pin "2") (pinfunction "2_2") (pintype "passive"))
    )
    (net (code "78") (name "Net-(B7-3A)") (class "Default")
      (node (ref "B7") (pin "9") (pinfunction "3A_9") (pintype "passive"))
      (node (ref "R51") (pin "2") (pinfunction "2_2") (pintype "passive"))
    )
    (net (code "79") (name "Net-(B7-4A)") (class "Default")
      (node (ref "B7") (pin "15") (pinfunction "4A_15") (pintype "passive"))
      (node (ref "R52") (pin "2") (pinfunction "2_2") (pintype "passive"))
    )
    (net (code "80") (name "Net-(B8-A)") (class "Default")
      (node (ref "B8") (pin "4") (pinfunction "A_4") (pintype "passive"))
      (node (ref "R57") (pin "2") (pinfunction "2_2") (pintype "passive"))
    )
    (net (code "81") (name "Net-(B8-B0)") (class "Default")
      (node (ref "B8") (pin "3") (pinfunction "B0_3") (pintype "passive"))
      (node (ref "R53") (pin "1") (pinfunction "1_1") (pintype "passive"))
    )
    (net (code "82") (name "Net-(B8-B1)") (class "Default")
      (node (ref "B8") (pin "1") (pinfunction "B1_1") (pintype "passive"))
      (node (ref "R55") (pin "1") (pinfunction "1_1") (pintype "passive"))
    )
    (net (code "83") (name "Net-(B8-S)") (class "Default")
      (node (ref "B8") (pin "6") (pinfunction "S_6") (pintype "passive"))
      (node (ref "R59") (pin "1") (pinfunction "1_1") (pintype "passive"))
    )
    (net (code "84") (name "Net-(B9-A)") (class "Default")
      (node (ref "B9") (pin "4") (pinfunction "A_4") (pintype "passive"))
      (node (ref "R58") (pin "2") (pinfunction "2_2") (pintype "passive"))
    )
    (net (code "85") (name "Net-(B9-B0)") (class "Default")
      (node (ref "B9") (pin "3") (pinfunction "B0_3") (pintype "passive"))
      (node (ref "R54") (pin "1") (pinfunction "1_1") (pintype "passive"))
    )
    (net (code "86") (name "Net-(B9-B1)") (class "Default")
      (node (ref "B9") (pin "1") (pinfunction "B1_1") (pintype "passive"))
      (node (ref "R56") (pin "1") (pinfunction "1_1") (pintype "passive"))
    )
    (net (code "87") (name "Net-(B9-S)") (class "Default")
      (node (ref "B9") (pin "6") (pinfunction "S_6") (pintype "passive"))
      (node (ref "R60") (pin "1") (pinfunction "1_1") (pintype "passive"))
    )
    (net (code "88") (name "Net-(B10-1A)") (class "Default")
      (node (ref "B10") (pin "1") (pinfunction "1A_1") (pintype "passive"))
      (node (ref "R61") (pin "2") (pinfunction "2_2") (pintype "passive"))
    )
    (net (code "89") (name "Net-(B10-2A)") (class "Default")
      (node (ref "B10") (pin "7") (pinfunction "2A_7") (pintype "passive"))
      (node (ref "R62") (pin "2") (pinfunction "2_2") (pintype "passive"))
    )
    (net (code "90") (name "Net-(B10-3A)") (class "Default")
      (node (ref "B10") (pin "9") (pinfunction "3A_9") (pintype "passive"))
      (node (ref "R63") (pin "2") (pinfunction "2_2") (pintype "passive"))
    )
    (net (code "91") (name "Net-(B10-4A)") (class "Default")
      (node (ref "B10") (pin "15") (pinfunction "4A_15") (pintype "passive"))
      (node (ref "R64") (pin "2") (pinfunction "2_2") (pintype "passive"))
    )
    (net (code "92") (name "Net-(H1-Pad1)") (class "Default")
      (node (ref "H1") (pin "1") (pinfunction "1_1") (pintype "passive"))
      (node (ref "R3") (pin "2") (pinfunction "2_2") (pintype "passive"))
    )
    (net (code "93") (name "Net-(H1-Pad3)") (class "Default")
      (node (ref "H1") (pin "3") (pinfunction "3_3") (pintype "passive"))
      (node (ref "R6") (pin "2") (pinfunction "2_2") (pintype "passive"))
    )
    (net (code "94") (name "Net-(H1-Pad5)") (class "Default")
      (node (ref "H1") (pin "5") (pinfunction "5_5") (pintype "passive"))
      (node (ref "R9") (pin "2") (pinfunction "2_2") (pintype "passive"))
    )
    (net (code "95") (name "Net-(H1-Pad7)") (class "Default")
      (node (ref "H1") (pin "7") (pinfunction "7_7") (pintype "passive"))
      (node (ref "R12") (pin "2") (pinfunction "2_2") (pintype "passive"))
    )
    (net (code "96") (name "Net-(H1-Pad9)") (class "Default")
      (node (ref "H1") (pin "9") (pinfunction "9_9") (pintype "passive"))
      (node (ref "R13") (pin "2") (pinfunction "2_2") (pintype "passive"))
    )
    (net (code "97") (name "Net-(H1-Pad11)") (class "Default")
      (node (ref "H1") (pin "11") (pinfunction "11_11") (pintype "passive"))
      (node (ref "R14") (pin "2") (pinfunction "2_2") (pintype "passive"))
    )
    (net (code "98") (name "Net-(H1-Pad13)") (class "Default")
      (node (ref "H1") (pin "13") (pinfunction "13_13") (pintype "passive"))
      (node (ref "R15") (pin "2") (pinfunction "2_2") (pintype "passive"))
    )
    (net (code "99") (name "Net-(H1-Pad15)") (class "Default")
      (node (ref "H1") (pin "15") (pinfunction "15_15") (pintype "passive"))
      (node (ref "R16") (pin "2") (pinfunction "2_2") (pintype "passive"))
    )
    (net (code "100") (name "Net-(H2-Pad1)") (class "Default")
      (node (ref "H2") (pin "1") (pinfunction "1_1") (pintype "passive"))
      (node (ref "R25") (pin "2") (pinfunction "2_2") (pintype "passive"))
    )
    (net (code "101") (name "Net-(H2-Pad2)") (class "Default")
      (node (ref "H2") (pin "2") (pinfunction "2_2") (pintype "passive"))
      (node (ref "R26") (pin "1") (pinfunction "1_1") (pintype "passive"))
    )
    (net (code "102") (name "Net-(H2-Pad3)") (class "Default")
      (node (ref "H2") (pin "3") (pinfunction "3_3") (pintype "passive"))
      (node (ref "R27") (pin "2") (pinfunction "2_2") (pintype "passive"))
    )
    (net (code "103") (name "Net-(H2-Pad4)") (class "Default")
      (node (ref "H2") (pin "4") (pinfunction "4_4") (pintype "passive"))
      (node (ref "R28") (pin "1") (pinfunction "1_1") (pintype "passive"))
    )
    (net (code "104") (name "Net-(H2-Pad5)") (class "Default")
      (node (ref "H2") (pin "5") (pinfunction "5_5") (pintype "passive"))
      (node (ref "R29") (pin "2") (pinfunction "2_2") (pintype "passive"))
    )
    (net (code "105") (name "Net-(H2-Pad6)") (class "Default")
      (node (ref "H2") (pin "6") (pinfunction "6_6") (pintype "passive"))
      (node (ref "R30") (pin "1") (pinfunction "1_1") (pintype "passive"))
    )
    (net (code "106") (name "Net-(H2-Pad7)") (class "Default")
      (node (ref "H2") (pin "7") (pinfunction "7_7") (pintype "passive"))
      (node (ref "R31") (pin "2") (pinfunction "2_2") (pintype "passive"))
    )
    (net (code "107") (name "Net-(H2-Pad8)") (class "Default")
      (node (ref "H2") (pin "8") (pinfunction "8_8") (pintype "passive"))
      (node (ref "R32") (pin "1") (pinfunction "1_1") (pintype "passive"))
    )
    (net (code "108") (name "Net-(H2-Pad9)") (class "Default")
      (node (ref "H2") (pin "9") (pinfunction "9_9") (pintype "passive"))
      (node (ref "R33") (pin "2") (pinfunction "2_2") (pintype "passive"))
    )
    (net (code "109") (name "Net-(H2-Pad10)") (class "Default")
      (node (ref "H2") (pin "10") (pinfunction "10_10") (pintype "passive"))
      (node (ref "R34") (pin "1") (pinfunction "1_1") (pintype "passive"))
    )
    (net (code "110") (name "Net-(H2-Pad11)") (class "Default")
      (node (ref "H2") (pin "11") (pinfunction "11_11") (pintype "passive"))
      (node (ref "R35") (pin "2") (pinfunction "2_2") (pintype "passive"))
    )
    (net (code "111") (name "Net-(H2-Pad12)") (class "Default")
      (node (ref "H2") (pin "12") (pinfunction "12_12") (pintype "passive"))
      (node (ref "R36") (pin "1") (pinfunction "1_1") (pintype "passive"))
    )
    (net (code "112") (name "Net-(H2-Pad13)") (class "Default")
      (node (ref "H2") (pin "13") (pinfunction "13_13") (pintype "passive"))
      (node (ref "R37") (pin "2") (pinfunction "2_2") (pintype "passive"))
    )
    (net (code "113") (name "Net-(H2-Pad14)") (class "Default")
      (node (ref "H2") (pin "14") (pinfunction "14_14") (pintype "passive"))
      (node (ref "R38") (pin "1") (pinfunction "1_1") (pintype "passive"))
    )
    (net (code "114") (name "Net-(H2-Pad15)") (class "Default")
      (node (ref "H2") (pin "15") (pinfunction "15_15") (pintype "passive"))
      (node (ref "R39") (pin "2") (pinfunction "2_2") (pintype "passive"))
    )
    (net (code "115") (name "Net-(H2-Pad16)") (class "Default")
      (node (ref "H2") (pin "16") (pinfunction "16_16") (pintype "passive"))
      (node (ref "R40") (pin "1") (pinfunction "1_1") (pintype "passive"))
    )
  )
)
